# control_board.net
KiCad netlist of a schematic drawn in EAGLE
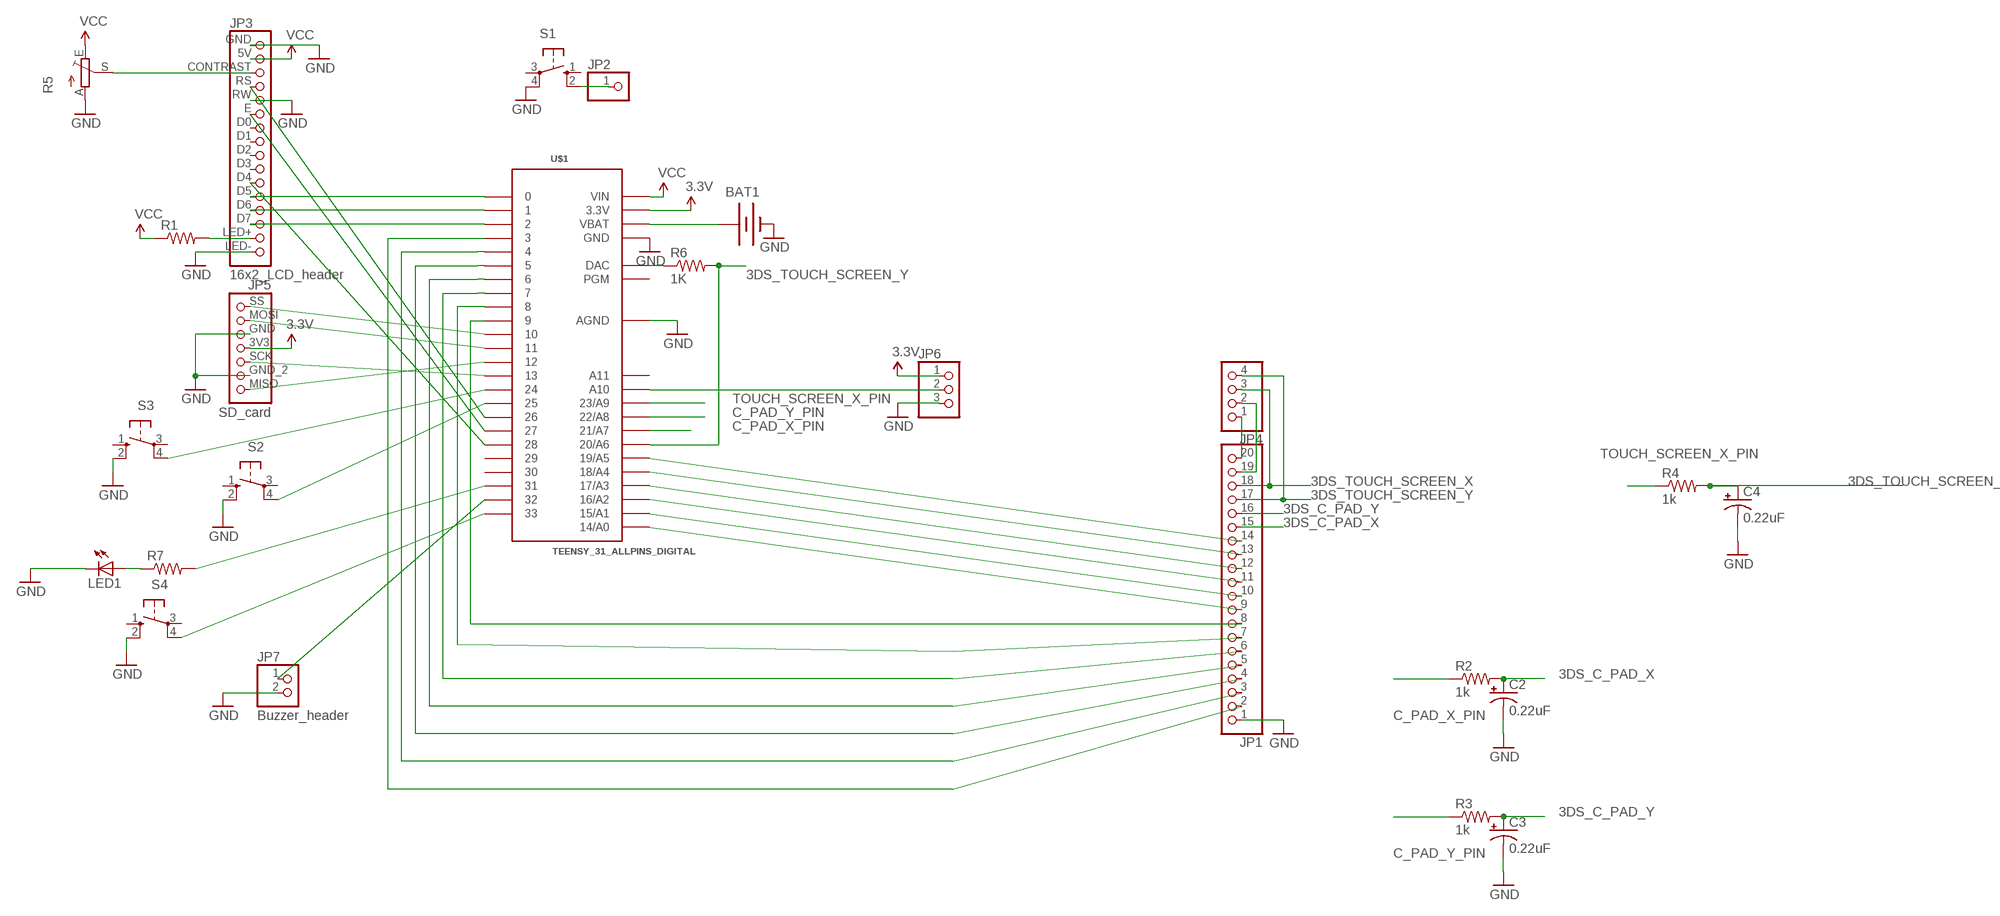
[diagram p0: schematic, sheet 1]

(export (version "E")
  (design (tool "Eeschema 10.0.6"))
  (components
    (comp (ref "BAT1")
      (value "BATTERY20PTH")
      (footprint "eagle-import:BATTCOM_20MM_PTH")
      (libsource (lib "eagle-import") (part "BATTERY20PTH"))
    )
    (comp (ref "C2")
      (value "0.22uF")
      (footprint "eagle-import:CPOL-RADIAL-10UF-25V")
      (libsource (lib "eagle-import") (part "10UF-25V-20%(PTH)"))
    )
    (comp (ref "C3")
      (value "0.22uF")
      (footprint "eagle-import:CPOL-RADIAL-10UF-25V")
      (libsource (lib "eagle-import") (part "10UF-25V-20%(PTH)"))
    )
    (comp (ref "C4")
      (value "0.22uF")
      (footprint "eagle-import:CPOL-RADIAL-10UF-25V")
      (libsource (lib "eagle-import") (part "10UF-25V-20%(PTH)"))
    )
    (comp (ref "JP1")
      (value "PINHD-1X20")
      (footprint "eagle-import:1X20")
      (libsource (lib "eagle-import") (part "PINHD-1X20"))
    )
    (comp (ref "JP2")
      (value "PINHD-1X1")
      (footprint "eagle-import:1X01")
      (libsource (lib "eagle-import") (part "PINHD-1X1"))
    )
    (comp (ref "JP3")
      (value "16x2_LCD_header")
      (footprint "eagle-import:1X16")
      (libsource (lib "eagle-import") (part "PINHD-1X16"))
    )
    (comp (ref "JP4")
      (value "PINHD-1X4")
      (footprint "eagle-import:1X04")
      (libsource (lib "eagle-import") (part "PINHD-1X4"))
    )
    (comp (ref "JP5")
      (value "SD_card")
      (footprint "eagle-import:1X07")
      (libsource (lib "eagle-import") (part "PINHD-1X7"))
    )
    (comp (ref "JP6")
      (value "PINHD-1X3")
      (footprint "eagle-import:1X03")
      (libsource (lib "eagle-import") (part "PINHD-1X3"))
    )
    (comp (ref "JP7")
      (value "Buzzer_header")
      (footprint "eagle-import:1X02")
      (libsource (lib "eagle-import") (part "PINHD-1X2"))
    )
    (comp (ref "LED1")
      (value "LED5MM")
      (footprint "eagle-import:LED5MM")
      (libsource (lib "eagle-import") (part "LED5MM"))
    )
    (comp (ref "R1")
      (value "RESISTOREZ")
      (footprint "eagle-import:AXIAL-0.3EZ")
      (libsource (lib "eagle-import") (part "RESISTOREZ"))
    )
    (comp (ref "R2")
      (value "1k")
      (footprint "eagle-import:AXIAL-0.1")
      (libsource (lib "eagle-import") (part "RESISTORPTH-1/4W-VERT"))
    )
    (comp (ref "R3")
      (value "1k")
      (footprint "eagle-import:AXIAL-0.1")
      (libsource (lib "eagle-import") (part "RESISTORPTH-1/4W-VERT"))
    )
    (comp (ref "R4")
      (value "1k")
      (footprint "eagle-import:AXIAL-0.1")
      (libsource (lib "eagle-import") (part "RESISTORPTH-1/4W-VERT"))
    )
    (comp (ref "R5")
      (value "TRIM_EU-CA6V")
      (footprint "eagle-import:CA6V")
      (libsource (lib "eagle-import") (part "TRIM_EU-CA6V"))
    )
    (comp (ref "R6")
      (value "1K")
      (footprint "eagle-import:AXIAL-0.1")
      (libsource (lib "eagle-import") (part "RESISTORPTH-1/4W-VERT"))
    )
    (comp (ref "R7")
      (value "RESISTOREZ")
      (footprint "eagle-import:AXIAL-0.3EZ")
      (libsource (lib "eagle-import") (part "RESISTOREZ"))
    )
    (comp (ref "S1")
      (value "10-XX")
      (footprint "eagle-import:B3F-10XX")
      (fields (field (name "MPN") "B3F-1000"))
      (libsource (lib "eagle-import") (part "10-XX"))
    )
    (comp (ref "S2")
      (value "10-XX")
      (footprint "eagle-import:B3F-10XX")
      (fields (field (name "MPN") "B3F-1000"))
      (libsource (lib "eagle-import") (part "10-XX"))
    )
    (comp (ref "S3")
      (value "10-XX")
      (footprint "eagle-import:B3F-10XX")
      (fields (field (name "MPN") "B3F-1000"))
      (libsource (lib "eagle-import") (part "10-XX"))
    )
    (comp (ref "S4")
      (value "10-XX")
      (footprint "eagle-import:B3F-10XX")
      (fields (field (name "MPN") "B3F-1000"))
      (libsource (lib "eagle-import") (part "10-XX"))
    )
    (comp (ref "U$1")
      (value "TEENSY_31_ALLPINS_DIGITAL")
      (footprint "eagle-import:TEENSY_31_ALLPINS_DIGITAL")
      (libsource (lib "eagle-import") (part "TEENSY_31_ALLPINS_DIGITAL"))
    )
  )
  (nets
    (net (code "1") (name "/3DS_C_PAD_X") (class "Default")
      (node (ref "C2") (pin "1") (pinfunction "+_1") (pintype "passive"))
      (node (ref "JP1") (pin "15") (pinfunction "15_15") (pintype "passive"))
      (node (ref "R2") (pin "P$2") (pinfunction "2_P$2") (pintype "passive"))
    )
    (net (code "2") (name "/3DS_C_PAD_Y") (class "Default")
      (node (ref "C3") (pin "1") (pinfunction "+_1") (pintype "passive"))
      (node (ref "JP1") (pin "16") (pinfunction "16_16") (pintype "passive"))
      (node (ref "R3") (pin "P$2") (pinfunction "2_P$2") (pintype "passive"))
    )
    (net (code "3") (name "/3DS_TOUCH_SCREEN_X") (class "Default")
      (node (ref "C4") (pin "1") (pinfunction "+_1") (pintype "passive"))
      (node (ref "JP1") (pin "18") (pinfunction "18_18") (pintype "passive"))
      (node (ref "JP4") (pin "3") (pinfunction "3_3") (pintype "passive"))
      (node (ref "R4") (pin "P$2") (pinfunction "2_P$2") (pintype "passive"))
    )
    (net (code "4") (name "/3DS_TOUCH_SCREEN_Y") (class "Default")
      (node (ref "JP1") (pin "17") (pinfunction "17_17") (pintype "passive"))
      (node (ref "JP4") (pin "4") (pinfunction "4_4") (pintype "passive"))
      (node (ref "R6") (pin "P$2") (pinfunction "2_P$2") (pintype "passive"))
      (node (ref "U$1") (pin "20/A6") (pinfunction "20/A6_20/A6") (pintype "bidirectional"))
    )
    (net (code "5") (name "/C_PAD_X_PIN") (class "Default")
      (node (ref "R2") (pin "P$1") (pinfunction "1_P$1") (pintype "passive"))
      (node (ref "U$1") (pin "21/A7") (pinfunction "21/A7_21/A7") (pintype "bidirectional"))
    )
    (net (code "6") (name "/C_PAD_Y_PIN") (class "Default")
      (node (ref "R3") (pin "P$1") (pinfunction "1_P$1") (pintype "passive"))
      (node (ref "U$1") (pin "22/A8") (pinfunction "22/A8_22/A8") (pintype "bidirectional"))
    )
    (net (code "7") (name "/TOUCH_SCREEN_X_PIN") (class "Default")
      (node (ref "R4") (pin "P$1") (pinfunction "1_P$1") (pintype "passive"))
      (node (ref "U$1") (pin "23/A9") (pinfunction "23/A9_23/A9") (pintype "bidirectional"))
    )
    (net (code "8") (name "3.3V") (class "Default")
      (node (ref "JP5") (pin "3V3") (pinfunction "4_3V3") (pintype "passive"))
      (node (ref "JP6") (pin "1") (pinfunction "1_1") (pintype "passive"))
      (node (ref "U$1") (pin "3.3V") (pinfunction "3.3V_3.3V") (pintype "power_in"))
    )
    (net (code "9") (name "GND") (class "Default")
      (node (ref "BAT1") (pin "2") (pinfunction "-_2") (pintype "power_in"))
      (node (ref "C2") (pin "2") (pinfunction "-_2") (pintype "passive"))
      (node (ref "C3") (pin "2") (pinfunction "-_2") (pintype "passive"))
      (node (ref "C4") (pin "2") (pinfunction "-_2") (pintype "passive"))
      (node (ref "JP1") (pin "1") (pinfunction "1_1") (pintype "passive"))
      (node (ref "JP3") (pin "GND") (pinfunction "GND_GND") (pintype "passive"))
      (node (ref "JP3") (pin "LED-") (pinfunction "LED-_LED-") (pintype "passive"))
      (node (ref "JP3") (pin "RW") (pinfunction "RW_RW") (pintype "passive"))
      (node (ref "JP5") (pin "GND") (pinfunction "3_GND") (pintype "passive"))
      (node (ref "JP5") (pin "GND_2") (pinfunction "6_GND_2") (pintype "passive"))
      (node (ref "JP6") (pin "3") (pinfunction "3_3") (pintype "passive"))
      (node (ref "JP7") (pin "2") (pinfunction "2_2") (pintype "passive"))
      (node (ref "LED1") (pin "K") (pinfunction "C_K") (pintype "passive"))
      (node (ref "R5") (pin "A") (pinfunction "A_A") (pintype "passive"))
      (node (ref "S1") (pin "4") (pinfunction "P1_4") (pintype "passive"))
      (node (ref "S2") (pin "2") (pinfunction "S1_2") (pintype "passive"))
      (node (ref "S3") (pin "2") (pinfunction "S1_2") (pintype "passive"))
      (node (ref "S4") (pin "2") (pinfunction "S1_2") (pintype "passive"))
      (node (ref "U$1") (pin "AGND") (pinfunction "AGND_AGND") (pintype "power_in"))
      (node (ref "U$1") (pin "GND") (pinfunction "GND_GND") (pintype "power_in"))
    )
    (net (code "10") (name "Net-(BAT1-+)") (class "Default")
      (node (ref "BAT1") (pin "1") (pinfunction "+_1") (pintype "power_in"))
      (node (ref "U$1") (pin "VBAT") (pinfunction "VBAT_VBAT") (pintype "power_in"))
    )
    (net (code "11") (name "Net-(JP1-Pad2)") (class "Default")
      (node (ref "JP1") (pin "2") (pinfunction "2_2") (pintype "passive"))
      (node (ref "U$1") (pin "3") (pinfunction "3_3") (pintype "bidirectional"))
    )
    (net (code "12") (name "Net-(JP1-Pad3)") (class "Default")
      (node (ref "JP1") (pin "3") (pinfunction "3_3") (pintype "passive"))
      (node (ref "U$1") (pin "4") (pinfunction "4_4") (pintype "bidirectional"))
    )
    (net (code "13") (name "Net-(JP1-Pad4)") (class "Default")
      (node (ref "JP1") (pin "4") (pinfunction "4_4") (pintype "passive"))
      (node (ref "U$1") (pin "5") (pinfunction "5_5") (pintype "bidirectional"))
    )
    (net (code "14") (name "Net-(JP1-Pad5)") (class "Default")
      (node (ref "JP1") (pin "5") (pinfunction "5_5") (pintype "passive"))
      (node (ref "U$1") (pin "6") (pinfunction "6_6") (pintype "bidirectional"))
    )
    (net (code "15") (name "Net-(JP1-Pad6)") (class "Default")
      (node (ref "JP1") (pin "6") (pinfunction "6_6") (pintype "passive"))
      (node (ref "U$1") (pin "7") (pinfunction "7_7") (pintype "bidirectional"))
    )
    (net (code "16") (name "Net-(JP1-Pad7)") (class "Default")
      (node (ref "JP1") (pin "7") (pinfunction "7_7") (pintype "passive"))
      (node (ref "U$1") (pin "8") (pinfunction "8_8") (pintype "bidirectional"))
    )
    (net (code "17") (name "Net-(JP1-Pad8)") (class "Default")
      (node (ref "JP1") (pin "8") (pinfunction "8_8") (pintype "passive"))
      (node (ref "U$1") (pin "9") (pinfunction "9_9") (pintype "bidirectional"))
    )
    (net (code "18") (name "Net-(JP1-Pad9)") (class "Default")
      (node (ref "JP1") (pin "9") (pinfunction "9_9") (pintype "passive"))
      (node (ref "U$1") (pin "14/A0") (pinfunction "14/A0_14/A0") (pintype "bidirectional"))
    )
    (net (code "19") (name "Net-(JP1-Pad10)") (class "Default")
      (node (ref "JP1") (pin "10") (pinfunction "10_10") (pintype "passive"))
      (node (ref "U$1") (pin "15/A1") (pinfunction "15/A1_15/A1") (pintype "bidirectional"))
    )
    (net (code "20") (name "Net-(JP1-Pad11)") (class "Default")
      (node (ref "JP1") (pin "11") (pinfunction "11_11") (pintype "passive"))
      (node (ref "U$1") (pin "16/A2") (pinfunction "16/A2_16/A2") (pintype "bidirectional"))
    )
    (net (code "21") (name "Net-(JP1-Pad12)") (class "Default")
      (node (ref "JP1") (pin "12") (pinfunction "12_12") (pintype "passive"))
      (node (ref "U$1") (pin "17/A3") (pinfunction "17/A3_17/A3") (pintype "bidirectional"))
    )
    (net (code "22") (name "Net-(JP1-Pad13)") (class "Default")
      (node (ref "JP1") (pin "13") (pinfunction "13_13") (pintype "passive"))
      (node (ref "U$1") (pin "18/A4") (pinfunction "18/A4_18/A4") (pintype "bidirectional"))
    )
    (net (code "23") (name "Net-(JP1-Pad14)") (class "Default")
      (node (ref "JP1") (pin "14") (pinfunction "14_14") (pintype "passive"))
      (node (ref "U$1") (pin "19/A5") (pinfunction "19/A5_19/A5") (pintype "bidirectional"))
    )
    (net (code "24") (name "Net-(JP1-Pad19)") (class "Default")
      (node (ref "JP1") (pin "19") (pinfunction "19_19") (pintype "passive"))
      (node (ref "JP4") (pin "2") (pinfunction "2_2") (pintype "passive"))
    )
    (net (code "25") (name "Net-(JP1-Pad20)") (class "Default")
      (node (ref "JP1") (pin "20") (pinfunction "20_20") (pintype "passive"))
      (node (ref "JP4") (pin "1") (pinfunction "1_1") (pintype "passive"))
    )
    (net (code "26") (name "Net-(JP3-PadCONTRAST)") (class "Default")
      (node (ref "JP3") (pin "CONTRAST") (pinfunction "CONTRAST_CONTRAST") (pintype "passive"))
      (node (ref "R5") (pin "S") (pinfunction "S_S") (pintype "passive"))
    )
    (net (code "27") (name "Net-(JP3-PadD4)") (class "Default")
      (node (ref "JP3") (pin "D4") (pinfunction "D4_D4") (pintype "passive"))
      (node (ref "U$1") (pin "28") (pinfunction "28_28") (pintype "bidirectional"))
    )
    (net (code "28") (name "Net-(JP3-PadD5)") (class "Default")
      (node (ref "JP3") (pin "D5") (pinfunction "D5_D5") (pintype "passive"))
      (node (ref "U$1") (pin "0") (pinfunction "0_0") (pintype "bidirectional"))
    )
    (net (code "29") (name "Net-(JP3-PadD6)") (class "Default")
      (node (ref "JP3") (pin "D6") (pinfunction "D6_D6") (pintype "passive"))
      (node (ref "U$1") (pin "1") (pinfunction "1_1") (pintype "bidirectional"))
    )
    (net (code "30") (name "Net-(JP3-PadD7)") (class "Default")
      (node (ref "JP3") (pin "D7") (pinfunction "D7_D7") (pintype "passive"))
      (node (ref "U$1") (pin "2") (pinfunction "2_2") (pintype "bidirectional"))
    )
    (net (code "31") (name "Net-(JP3-PadE)") (class "Default")
      (node (ref "JP3") (pin "E") (pinfunction "E_E") (pintype "passive"))
      (node (ref "U$1") (pin "27") (pinfunction "27_27") (pintype "bidirectional"))
    )
    (net (code "32") (name "Net-(JP3-PadRS)") (class "Default")
      (node (ref "JP3") (pin "RS") (pinfunction "RS_RS") (pintype "passive"))
      (node (ref "U$1") (pin "26") (pinfunction "26_26") (pintype "bidirectional"))
    )
    (net (code "33") (name "Net-(JP5-1)") (class "Default")
      (node (ref "JP5") (pin "SS") (pinfunction "1_SS") (pintype "passive"))
      (node (ref "U$1") (pin "10") (pinfunction "10_10") (pintype "bidirectional"))
    )
    (net (code "34") (name "Net-(JP5-2)") (class "Default")
      (node (ref "JP5") (pin "MOSI") (pinfunction "2_MOSI") (pintype "passive"))
      (node (ref "U$1") (pin "11") (pinfunction "11_11") (pintype "bidirectional"))
    )
    (net (code "35") (name "Net-(JP5-5)") (class "Default")
      (node (ref "JP5") (pin "SCK") (pinfunction "5_SCK") (pintype "passive"))
      (node (ref "U$1") (pin "13") (pinfunction "13_13") (pintype "bidirectional"))
    )
    (net (code "36") (name "Net-(JP5-7)") (class "Default")
      (node (ref "JP5") (pin "MISO") (pinfunction "7_MISO") (pintype "passive"))
      (node (ref "U$1") (pin "12") (pinfunction "12_12") (pintype "bidirectional"))
    )
    (net (code "37") (name "Net-(JP6-Pad2)") (class "Default")
      (node (ref "JP6") (pin "2") (pinfunction "2_2") (pintype "passive"))
      (node (ref "U$1") (pin "A10") (pinfunction "A10_A10") (pintype "bidirectional"))
    )
    (net (code "38") (name "Net-(JP7-Pad1)") (class "Default")
      (node (ref "JP7") (pin "1") (pinfunction "1_1") (pintype "passive"))
      (node (ref "U$1") (pin "32") (pinfunction "32_32") (pintype "bidirectional"))
    )
    (net (code "39") (name "Net-(R1-2)") (class "Default")
      (node (ref "JP3") (pin "LED+") (pinfunction "LED+_LED+") (pintype "passive"))
      (node (ref "R1") (pin "P$2") (pinfunction "2_P$2") (pintype "passive"))
    )
    (net (code "40") (name "Net-(R6-1)") (class "Default")
      (node (ref "R6") (pin "P$1") (pinfunction "1_P$1") (pintype "passive"))
      (node (ref "U$1") (pin "RESET") (pinfunction "DAC_RESET") (pintype "bidirectional"))
    )
    (net (code "41") (name "Net-(R7-1)") (class "Default")
      (node (ref "LED1") (pin "A") (pinfunction "A_A") (pintype "passive"))
      (node (ref "R7") (pin "P$1") (pinfunction "1_P$1") (pintype "passive"))
    )
    (net (code "42") (name "Net-(R7-2)") (class "Default")
      (node (ref "R7") (pin "P$2") (pinfunction "2_P$2") (pintype "passive"))
      (node (ref "U$1") (pin "31") (pinfunction "31_31") (pintype "bidirectional"))
    )
    (net (code "43") (name "Net-(S1-S1)") (class "Default")
      (node (ref "JP2") (pin "1") (pinfunction "1_1") (pintype "passive"))
      (node (ref "S1") (pin "2") (pinfunction "S1_2") (pintype "passive"))
    )
    (net (code "44") (name "Net-(S2-P1)") (class "Default")
      (node (ref "S2") (pin "4") (pinfunction "P1_4") (pintype "passive"))
      (node (ref "U$1") (pin "25") (pinfunction "25_25") (pintype "bidirectional"))
    )
    (net (code "45") (name "Net-(S3-P1)") (class "Default")
      (node (ref "S3") (pin "4") (pinfunction "P1_4") (pintype "passive"))
      (node (ref "U$1") (pin "24") (pinfunction "24_24") (pintype "bidirectional"))
    )
    (net (code "46") (name "Net-(S4-P1)") (class "Default")
      (node (ref "S4") (pin "4") (pinfunction "P1_4") (pintype "passive"))
      (node (ref "U$1") (pin "33") (pinfunction "33_33") (pintype "bidirectional"))
    )
    (net (code "47") (name "VCC") (class "Default")
      (node (ref "JP3") (pin "5V") (pinfunction "5V_5V") (pintype "passive"))
      (node (ref "R1") (pin "P$1") (pinfunction "1_P$1") (pintype "passive"))
      (node (ref "R5") (pin "E") (pinfunction "E_E") (pintype "passive"))
      (node (ref "U$1") (pin "VIN") (pinfunction "VIN_VIN") (pintype "power_in"))
    )
    (net (code "48") (name "unconnected-(JP3-PadD0)") (class "Default")
      (node (ref "JP3") (pin "D0") (pinfunction "D0_D0") (pintype "passive"))
    )
    (net (code "49") (name "unconnected-(JP3-PadD1)") (class "Default")
      (node (ref "JP3") (pin "D1") (pinfunction "D1_D1") (pintype "passive"))
    )
    (net (code "50") (name "unconnected-(JP3-PadD2)") (class "Default")
      (node (ref "JP3") (pin "D2") (pinfunction "D2_D2") (pintype "passive"))
    )
    (net (code "51") (name "unconnected-(JP3-PadD3)") (class "Default")
      (node (ref "JP3") (pin "D3") (pinfunction "D3_D3") (pintype "passive"))
    )
    (net (code "52") (name "unconnected-(S1-P-Pad3)") (class "Default")
      (node (ref "S1") (pin "3") (pinfunction "P_3") (pintype "passive"))
    )
    (net (code "53") (name "unconnected-(S1-S-Pad1)") (class "Default")
      (node (ref "S1") (pin "1") (pinfunction "S_1") (pintype "passive"))
    )
    (net (code "54") (name "unconnected-(S2-P-Pad3)") (class "Default")
      (node (ref "S2") (pin "3") (pinfunction "P_3") (pintype "passive"))
    )
    (net (code "55") (name "unconnected-(S2-S-Pad1)") (class "Default")
      (node (ref "S2") (pin "1") (pinfunction "S_1") (pintype "passive"))
    )
    (net (code "56") (name "unconnected-(S3-P-Pad3)") (class "Default")
      (node (ref "S3") (pin "3") (pinfunction "P_3") (pintype "passive"))
    )
    (net (code "57") (name "unconnected-(S3-S-Pad1)") (class "Default")
      (node (ref "S3") (pin "1") (pinfunction "S_1") (pintype "passive"))
    )
    (net (code "58") (name "unconnected-(S4-P-Pad3)") (class "Default")
      (node (ref "S4") (pin "3") (pinfunction "P_3") (pintype "passive"))
    )
    (net (code "59") (name "unconnected-(S4-S-Pad1)") (class "Default")
      (node (ref "S4") (pin "1") (pinfunction "S_1") (pintype "passive"))
    )
    (net (code "60") (name "unconnected-(U$1-Pad29)") (class "Default")
      (node (ref "U$1") (pin "29") (pinfunction "29_29") (pintype "bidirectional"))
    )
    (net (code "61") (name "unconnected-(U$1-Pad30)") (class "Default")
      (node (ref "U$1") (pin "30") (pinfunction "30_30") (pintype "bidirectional"))
    )
    (net (code "62") (name "unconnected-(U$1-PadA11)") (class "Default")
      (node (ref "U$1") (pin "A11") (pinfunction "A11_A11") (pintype "bidirectional"))
    )
    (net (code "63") (name "unconnected-(U$1-PadPGM)") (class "Default")
      (node (ref "U$1") (pin "PGM") (pinfunction "PGM_PGM") (pintype "bidirectional"))
    )
  )
)
